# Peripherals.net
KiCad netlist of a schematic drawn in Altium Designer
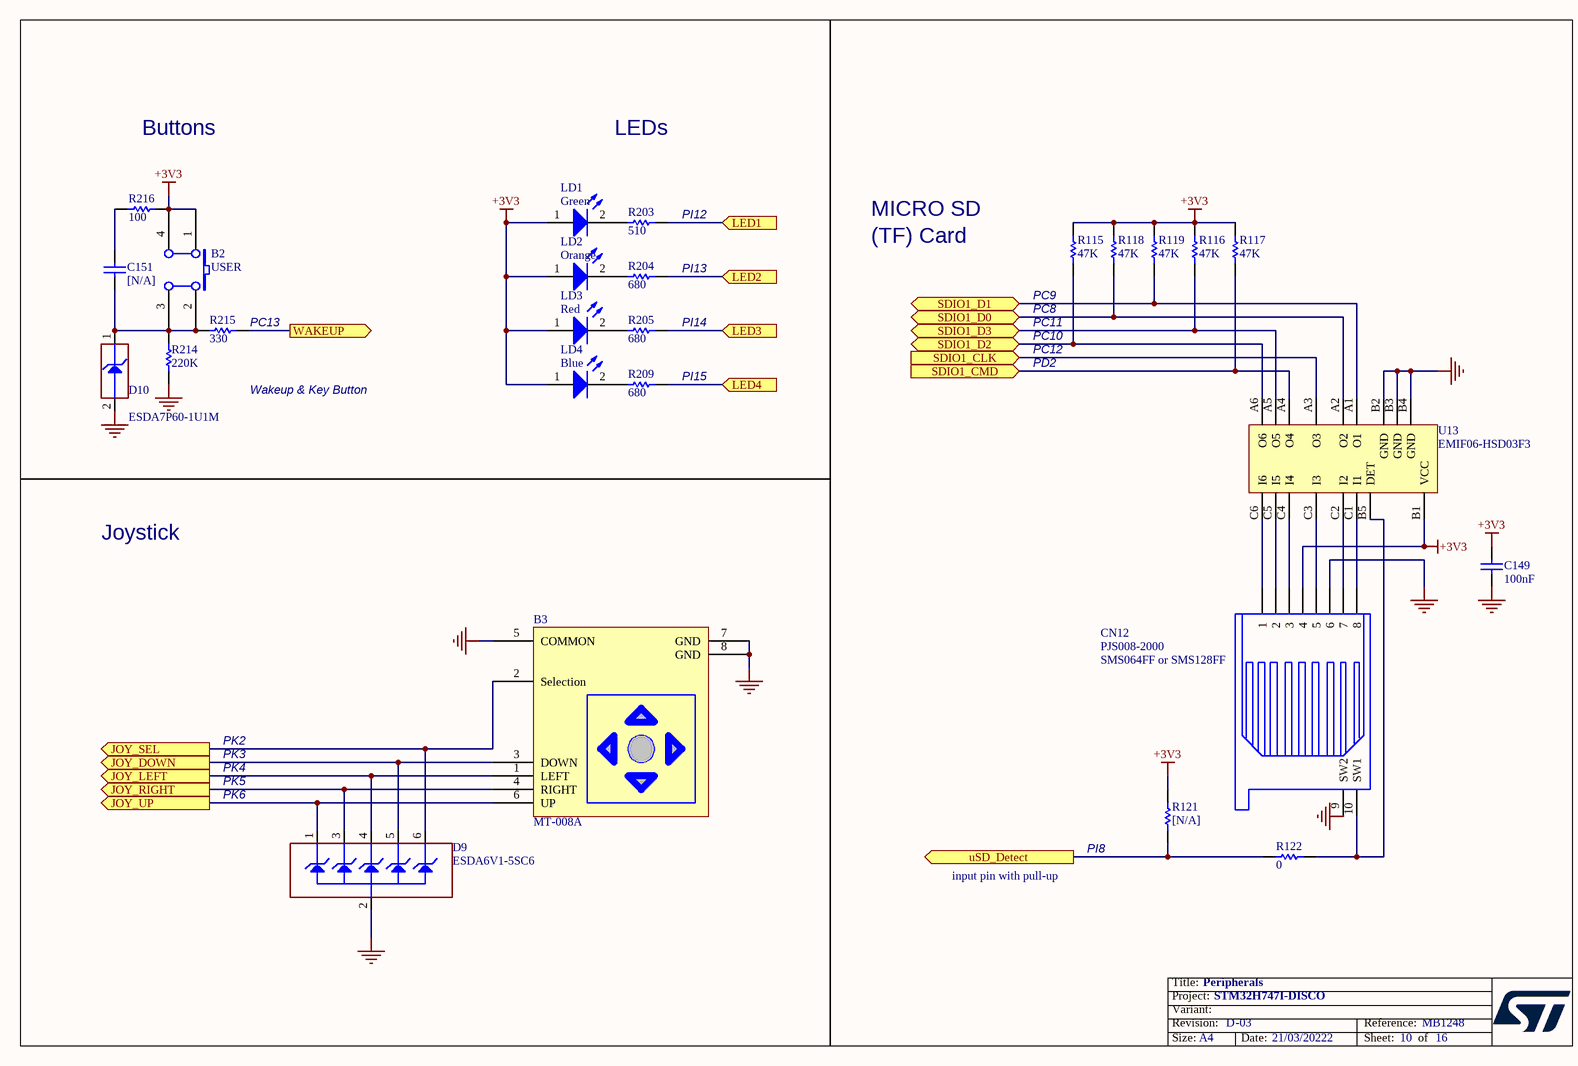
[diagram p0: Peripherals.SchDoc]

(export (version "E")
  (design (tool "Eeschema 10.0.6"))
  (components
    (comp (ref "B2")
      (value "USER")
      (footprint "PB10")
      (description "SE PUSHBUTTON")
      (libsource (lib "Documents") (part "SW PUSHBUTTON"))
    )
    (comp (ref "B3") (value "MT-008A") (footprint "MT-008A") (libsource (lib "MB1248") (part "MT-008A")))
    (comp (ref "C149")
      (value "100nF")
      (footprint "0603C")
      (description "Capacitor")
      (fields (field (name "PUBLISHER") "Altium Limited"))
      (libsource (lib "Miscellaneous Devices") (part "CAP"))
    )
    (comp (ref "C151")
      (value "[N/A]")
      (footprint "0603C")
      (description "Capacitor")
      (fields (field (name "PUBLISHER") "Altium Limited"))
      (libsource (lib "Miscellaneous Devices") (part "cap"))
    )
    (comp (ref "CN12")
      (value "PJS008-2000")
      (footprint "MSD_PJS008_")
      (libsource (lib "MB525") (part "SMS016AFA5E"))
    )
    (comp (ref "D9")
      (value "ESDA6V1-5SC6")
      (footprint "STM-SMEE:SOT23-6L")
      (description "5-line ESD protection")
      (libsource (lib "MB1248_1") (part "ESDA6V1-5SC6"))
    )
    (comp (ref "D10")
      (value "ESDA7P60-1U1M")
      (footprint "DO_2SM_1R6X1_21")
      (description "Dual Transil array for ESD protection")
      (libsource (lib "MCD_TEMP_PCH") (part "ESDALC6V1-1U2"))
    )
    (comp (ref "LD1")
      (value "Green")
      (footprint "0603D")
      (description "Typical RED, GREEN, YELLOW, AMBER GaAs LED")
      (fields (field (name "PUBLISHER") "Altium Limited"))
      (libsource (lib "Miscellaneous Devices") (part "LED2"))
    )
    (comp (ref "LD2")
      (value "Orange")
      (footprint "0603D")
      (description "Typical RED, GREEN, YELLOW, AMBER GaAs LED")
      (fields (field (name "PUBLISHER") "Altium Limited"))
      (libsource (lib "Miscellaneous Devices") (part "LED2"))
    )
    (comp (ref "LD3")
      (value "Red")
      (footprint "0603D")
      (description "Typical RED, GREEN, YELLOW, AMBER GaAs LED")
      (fields (field (name "PUBLISHER") "Altium Limited"))
      (libsource (lib "Miscellaneous Devices") (part "LED2"))
    )
    (comp (ref "LD4")
      (value "Blue")
      (footprint "0603D")
      (description "Typical RED, GREEN, YELLOW, AMBER GaAs LED")
      (fields (field (name "PUBLISHER") "Altium Limited"))
      (libsource (lib "Miscellaneous Devices") (part "LED2"))
    )
    (comp (ref "R115")
      (value "47K")
      (footprint "0603R")
      (description "Resistor")
      (fields (field (name "PUBLISHER") "Altium Limited"))
      (libsource (lib "Miscellaneous Devices") (part "res1"))
    )
    (comp (ref "R116")
      (value "47K")
      (footprint "0603R")
      (description "Resistor")
      (fields (field (name "PUBLISHER") "Altium Limited"))
      (libsource (lib "Miscellaneous Devices") (part "res1"))
    )
    (comp (ref "R117")
      (value "47K")
      (footprint "0603R")
      (description "Resistor")
      (fields (field (name "PUBLISHER") "Altium Limited"))
      (libsource (lib "Miscellaneous Devices") (part "res1"))
    )
    (comp (ref "R118")
      (value "47K")
      (footprint "0603R")
      (description "Resistor")
      (fields (field (name "PUBLISHER") "Altium Limited"))
      (libsource (lib "Miscellaneous Devices") (part "res1"))
    )
    (comp (ref "R119")
      (value "47K")
      (footprint "0603R")
      (description "Resistor")
      (fields (field (name "PUBLISHER") "Altium Limited"))
      (libsource (lib "Miscellaneous Devices") (part "res1"))
    )
    (comp (ref "R121")
      (value "[N/A]")
      (footprint "0603R")
      (description "Resistor")
      (fields (field (name "PUBLISHER") "Altium Limited"))
      (libsource (lib "Miscellaneous Devices") (part "res1"))
    )
    (comp (ref "R122")
      (value "0")
      (footprint "0603R")
      (description "Resistor")
      (fields (field (name "PUBLISHER") "Altium Limited"))
      (libsource (lib "Miscellaneous Devices") (part "Res1"))
    )
    (comp (ref "R203")
      (value "510")
      (footprint "0603R")
      (description "Resistor")
      (fields (field (name "PUBLISHER") "Altium Limited"))
      (libsource (lib "Miscellaneous Devices") (part "Res1"))
    )
    (comp (ref "R204")
      (value "680")
      (footprint "0603R")
      (description "Resistor")
      (fields (field (name "PUBLISHER") "Altium Limited"))
      (libsource (lib "Miscellaneous Devices") (part "Res1"))
    )
    (comp (ref "R205")
      (value "680")
      (footprint "0603R")
      (description "Resistor")
      (fields (field (name "PUBLISHER") "Altium Limited"))
      (libsource (lib "Miscellaneous Devices") (part "Res1"))
    )
    (comp (ref "R209")
      (value "680")
      (footprint "0603R")
      (description "Resistor")
      (fields (field (name "PUBLISHER") "Altium Limited"))
      (libsource (lib "Miscellaneous Devices") (part "Res1"))
    )
    (comp (ref "R214")
      (value "220K")
      (footprint "0603R")
      (description "Resistor")
      (fields (field (name "PUBLISHER") "Altium Limited"))
      (libsource (lib "Miscellaneous Devices") (part "res1"))
    )
    (comp (ref "R215")
      (value "330")
      (footprint "0603R")
      (description "Resistor")
      (fields (field (name "PUBLISHER") "Altium Limited"))
      (libsource (lib "Miscellaneous Devices") (part "Res1"))
    )
    (comp (ref "R216")
      (value "100")
      (footprint "0603R")
      (description "Resistor")
      (fields (field (name "PUBLISHER") "Altium Limited"))
      (libsource (lib "Miscellaneous Devices") (part "Res1"))
    )
    (comp (ref "U13")
      (value "EMIF06-HSD03F3")
      (footprint "FBGA17_0R4_1R1X2R4")
      (description "EMI filter with integrated ESD protection for micro-SD Card™")
      (libsource (lib "MB1248_1") (part "EMIF06-HSD03F3"))
    )
  )
  (nets
    (net (code "1") (name "+3V3") (class "Default")
      (node (ref "B2") (pin "1") (pinfunction "A0_1") (pintype "passive"))
      (node (ref "B2") (pin "4") (pinfunction "A1_4") (pintype "passive"))
      (node (ref "C149") (pin "1") (pinfunction "1_1") (pintype "passive"))
      (node (ref "CN12") (pin "4") (pinfunction "4_4") (pintype "passive"))
      (node (ref "LD1") (pin "1") (pinfunction "A_1") (pintype "passive"))
      (node (ref "LD2") (pin "1") (pinfunction "A_1") (pintype "passive"))
      (node (ref "LD3") (pin "1") (pinfunction "A_1") (pintype "passive"))
      (node (ref "LD4") (pin "1") (pinfunction "A_1") (pintype "passive"))
      (node (ref "R115") (pin "1") (pinfunction "1_1") (pintype "passive"))
      (node (ref "R116") (pin "1") (pinfunction "1_1") (pintype "passive"))
      (node (ref "R117") (pin "1") (pinfunction "1_1") (pintype "passive"))
      (node (ref "R118") (pin "1") (pinfunction "1_1") (pintype "passive"))
      (node (ref "R119") (pin "1") (pinfunction "1_1") (pintype "passive"))
      (node (ref "R121") (pin "2") (pinfunction "2_2") (pintype "passive"))
      (node (ref "R216") (pin "1") (pinfunction "1_1") (pintype "passive"))
      (node (ref "U13") (pin "B1") (pinfunction "VCC_B1") (pintype "passive"))
    )
    (net (code "2") (name "/JOY_DOWN") (class "Default")
      (node (ref "B3") (pin "3") (pinfunction "DOWN_3") (pintype "passive"))
      (node (ref "D9") (pin "5") (pinfunction "IO4_5") (pintype "passive"))
    )
    (net (code "3") (name "/JOY_LEFT") (class "Default")
      (node (ref "B3") (pin "1") (pinfunction "LEFT_1") (pintype "passive"))
      (node (ref "D9") (pin "4") (pinfunction "IO3_4") (pintype "passive"))
    )
    (net (code "4") (name "/JOY_RIGHT") (class "Default")
      (node (ref "B3") (pin "4") (pinfunction "RIGHT_4") (pintype "passive"))
      (node (ref "D9") (pin "3") (pinfunction "IO2_3") (pintype "passive"))
    )
    (net (code "5") (name "/JOY_SEL") (class "Default")
      (node (ref "B3") (pin "2") (pinfunction "Selection_2") (pintype "passive"))
      (node (ref "D9") (pin "6") (pinfunction "IO5_6") (pintype "passive"))
    )
    (net (code "6") (name "/JOY_UP") (class "Default")
      (node (ref "B3") (pin "6") (pinfunction "UP_6") (pintype "passive"))
      (node (ref "D9") (pin "1") (pinfunction "IO1_1") (pintype "passive"))
    )
    (net (code "7") (name "/LED1") (class "Default")
      (node (ref "R203") (pin "1") (pinfunction "1_1") (pintype "passive"))
    )
    (net (code "8") (name "/LED2") (class "Default")
      (node (ref "R204") (pin "1") (pinfunction "1_1") (pintype "passive"))
    )
    (net (code "9") (name "/LED3") (class "Default")
      (node (ref "R205") (pin "1") (pinfunction "1_1") (pintype "passive"))
    )
    (net (code "10") (name "/LED4") (class "Default")
      (node (ref "R209") (pin "1") (pinfunction "1_1") (pintype "passive"))
    )
    (net (code "11") (name "/SDIO1_CLK") (class "Default")
      (node (ref "U13") (pin "A3") (pinfunction "O3_A3") (pintype "passive"))
    )
    (net (code "12") (name "/SDIO1_CMD") (class "Default")
      (node (ref "R117") (pin "2") (pinfunction "2_2") (pintype "passive"))
      (node (ref "U13") (pin "A4") (pinfunction "O4_A4") (pintype "passive"))
    )
    (net (code "13") (name "/SDIO1_D0") (class "Default")
      (node (ref "R118") (pin "2") (pinfunction "2_2") (pintype "passive"))
      (node (ref "U13") (pin "A2") (pinfunction "O2_A2") (pintype "passive"))
    )
    (net (code "14") (name "/SDIO1_D1") (class "Default")
      (node (ref "R119") (pin "2") (pinfunction "2_2") (pintype "passive"))
      (node (ref "U13") (pin "A1") (pinfunction "O1_A1") (pintype "passive"))
    )
    (net (code "15") (name "/SDIO1_D2") (class "Default")
      (node (ref "R115") (pin "2") (pinfunction "2_2") (pintype "passive"))
      (node (ref "U13") (pin "A6") (pinfunction "O6_A6") (pintype "passive"))
    )
    (net (code "16") (name "/SDIO1_D3") (class "Default")
      (node (ref "R116") (pin "2") (pinfunction "2_2") (pintype "passive"))
      (node (ref "U13") (pin "A5") (pinfunction "O5_A5") (pintype "passive"))
    )
    (net (code "17") (name "/WAKEUP") (class "Default")
      (node (ref "R215") (pin "2") (pinfunction "2_2") (pintype "passive"))
    )
    (net (code "18") (name "/uSD_Detect") (class "Default")
      (node (ref "R121") (pin "1") (pinfunction "1_1") (pintype "passive"))
      (node (ref "R122") (pin "1") (pinfunction "1_1") (pintype "passive"))
    )
    (net (code "19") (name "GND") (class "Default")
      (node (ref "B3") (pin "5") (pinfunction "COMMON_5") (pintype "passive"))
      (node (ref "B3") (pin "7") (pinfunction "GND_7") (pintype "passive"))
      (node (ref "B3") (pin "8") (pinfunction "GND_8") (pintype "passive"))
      (node (ref "C149") (pin "2") (pinfunction "2_2") (pintype "passive"))
      (node (ref "CN12") (pin "6") (pinfunction "6_6") (pintype "passive"))
      (node (ref "CN12") (pin "9") (pinfunction "SW2_9") (pintype "passive"))
      (node (ref "D10") (pin "2") (pinfunction "GND_2") (pintype "passive"))
      (node (ref "D9") (pin "2") (pinfunction "GND_2") (pintype "passive"))
      (node (ref "R214") (pin "2") (pinfunction "2_2") (pintype "passive"))
      (node (ref "U13") (pin "B2") (pinfunction "GND_B2") (pintype "passive"))
      (node (ref "U13") (pin "B3") (pinfunction "GND_B3") (pintype "passive"))
      (node (ref "U13") (pin "B4") (pinfunction "GND_B4") (pintype "passive"))
    )
    (net (code "20") (name "Net-(B2-B0)") (class "Default")
      (node (ref "B2") (pin "2") (pinfunction "B0_2") (pintype "passive"))
      (node (ref "B2") (pin "3") (pinfunction "B1_3") (pintype "passive"))
      (node (ref "C151") (pin "1") (pinfunction "1_1") (pintype "passive"))
      (node (ref "D10") (pin "1") (pinfunction "IO1_1") (pintype "passive"))
      (node (ref "R214") (pin "1") (pinfunction "1_1") (pintype "passive"))
      (node (ref "R215") (pin "1") (pinfunction "1_1") (pintype "passive"))
    )
    (net (code "21") (name "Net-(C151-Pad2)") (class "Default")
      (node (ref "C151") (pin "2") (pinfunction "2_2") (pintype "passive"))
      (node (ref "R216") (pin "2") (pinfunction "2_2") (pintype "passive"))
    )
    (net (code "22") (name "Net-(CN12-SW1)") (class "Default")
      (node (ref "CN12") (pin "10") (pinfunction "SW1_10") (pintype "passive"))
      (node (ref "R122") (pin "2") (pinfunction "2_2") (pintype "passive"))
      (node (ref "U13") (pin "B5") (pinfunction "DET_B5") (pintype "passive"))
    )
    (net (code "23") (name "Net-(LD1-K)") (class "Default")
      (node (ref "LD1") (pin "2") (pinfunction "K_2") (pintype "passive"))
      (node (ref "R203") (pin "2") (pinfunction "2_2") (pintype "passive"))
    )
    (net (code "24") (name "Net-(LD2-K)") (class "Default")
      (node (ref "LD2") (pin "2") (pinfunction "K_2") (pintype "passive"))
      (node (ref "R204") (pin "2") (pinfunction "2_2") (pintype "passive"))
    )
    (net (code "25") (name "Net-(LD3-K)") (class "Default")
      (node (ref "LD3") (pin "2") (pinfunction "K_2") (pintype "passive"))
      (node (ref "R205") (pin "2") (pinfunction "2_2") (pintype "passive"))
    )
    (net (code "26") (name "Net-(LD4-K)") (class "Default")
      (node (ref "LD4") (pin "2") (pinfunction "K_2") (pintype "passive"))
      (node (ref "R209") (pin "2") (pinfunction "2_2") (pintype "passive"))
    )
    (net (code "27") (name "Net-(U13-I1)") (class "Default")
      (node (ref "CN12") (pin "8") (pinfunction "8_8") (pintype "passive"))
      (node (ref "U13") (pin "C1") (pinfunction "I1_C1") (pintype "passive"))
    )
    (net (code "28") (name "Net-(U13-I2)") (class "Default")
      (node (ref "CN12") (pin "7") (pinfunction "7_7") (pintype "passive"))
      (node (ref "U13") (pin "C2") (pinfunction "I2_C2") (pintype "passive"))
    )
    (net (code "29") (name "Net-(U13-I3)") (class "Default")
      (node (ref "CN12") (pin "5") (pinfunction "5_5") (pintype "passive"))
      (node (ref "U13") (pin "C3") (pinfunction "I3_C3") (pintype "passive"))
    )
    (net (code "30") (name "Net-(U13-I4)") (class "Default")
      (node (ref "CN12") (pin "3") (pinfunction "3_3") (pintype "passive"))
      (node (ref "U13") (pin "C4") (pinfunction "I4_C4") (pintype "passive"))
    )
    (net (code "31") (name "Net-(U13-I5)") (class "Default")
      (node (ref "CN12") (pin "2") (pinfunction "2_2") (pintype "passive"))
      (node (ref "U13") (pin "C5") (pinfunction "I5_C5") (pintype "passive"))
    )
    (net (code "32") (name "Net-(U13-I6)") (class "Default")
      (node (ref "CN12") (pin "1") (pinfunction "1_1") (pintype "passive"))
      (node (ref "U13") (pin "C6") (pinfunction "I6_C6") (pintype "passive"))
    )
  )
)
